# Sensor_Board_Schematic.net
KiCad netlist of a schematic drawn in Altium Designer
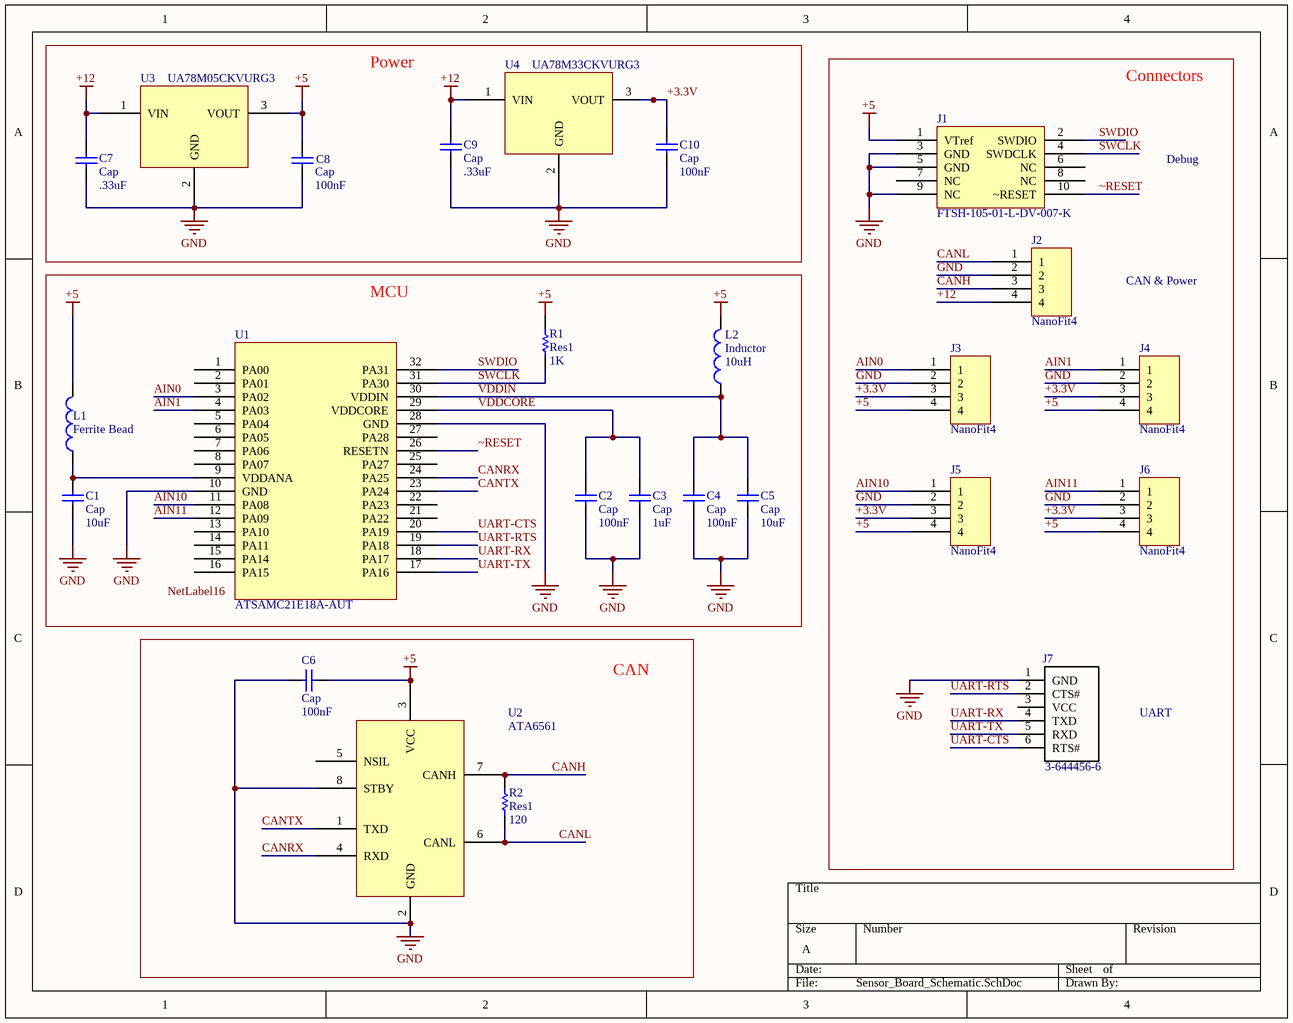
[diagram p0: Sensor_Board_Schematic.SchDoc]

(export (version "E")
  (design (tool "Eeschema 10.0.6"))
  (components
    (comp (ref "C1")
      (value "Cap")
      (footprint "Sensor_Board_Footprints:CAPC1608X08N")
      (description "Capacitor")
      (fields (field (name "ALTIUM_VALUE") "10uF") (field (name "PUBLISHER") "Altium Limited"))
      (libsource (lib "Miscellaneous Devices") (part "Cap"))
    )
    (comp (ref "C2")
      (value "Cap")
      (footprint "Sensor_Board_Footprints:CAPC1608X08N")
      (description "Capacitor")
      (fields (field (name "ALTIUM_VALUE") "100nF") (field (name "PUBLISHER") "Altium Limited"))
      (libsource (lib "Miscellaneous Devices") (part "Cap"))
    )
    (comp (ref "C3")
      (value "Cap")
      (footprint "Sensor_Board_Footprints:CAPC1608X08N")
      (description "Capacitor")
      (fields (field (name "ALTIUM_VALUE") "1uF") (field (name "PUBLISHER") "Altium Limited"))
      (libsource (lib "Miscellaneous Devices") (part "Cap"))
    )
    (comp (ref "C4")
      (value "Cap")
      (footprint "Sensor_Board_Footprints:CAPC1608X08N")
      (description "Capacitor")
      (fields (field (name "ALTIUM_VALUE") "100nF") (field (name "PUBLISHER") "Altium Limited"))
      (libsource (lib "Miscellaneous Devices") (part "Cap"))
    )
    (comp (ref "C5")
      (value "Cap")
      (footprint "Sensor_Board_Footprints:CAPC1608X08N")
      (description "Capacitor")
      (fields (field (name "ALTIUM_VALUE") "10uF") (field (name "PUBLISHER") "Altium Limited"))
      (libsource (lib "Miscellaneous Devices") (part "Cap"))
    )
    (comp (ref "C6")
      (value "Cap")
      (footprint "Sensor_Board_Footprints:CAPC1608X08N")
      (description "Capacitor")
      (fields (field (name "ALTIUM_VALUE") "100nF") (field (name "PUBLISHER") "Altium Limited"))
      (libsource (lib "Miscellaneous Devices") (part "Cap"))
    )
    (comp (ref "C7")
      (value "Cap")
      (footprint "Footprints:CAPC1608X08N")
      (description "Capacitor")
      (fields (field (name "ALTIUM_VALUE") ".33uF") (field (name "PUBLISHER") "Altium Limited"))
      (libsource (lib "Miscellaneous Devices") (part "Cap"))
    )
    (comp (ref "C8")
      (value "Cap")
      (footprint "Sensor_Board_Footprints:CAPC1608X08N")
      (description "Capacitor")
      (fields (field (name "ALTIUM_VALUE") "100nF") (field (name "PUBLISHER") "Altium Limited"))
      (libsource (lib "Miscellaneous Devices") (part "Cap"))
    )
    (comp (ref "C9")
      (value "Cap")
      (footprint "Footprints:CAPC1608X08N")
      (description "Capacitor")
      (fields (field (name "ALTIUM_VALUE") ".33uF") (field (name "PUBLISHER") "Altium Limited"))
      (libsource (lib "Miscellaneous Devices") (part "Cap"))
    )
    (comp (ref "C10")
      (value "Cap")
      (footprint "Footprints:CAPC1608X08N")
      (description "Capacitor")
      (fields (field (name "ALTIUM_VALUE") "100nF") (field (name "PUBLISHER") "Altium Limited"))
      (libsource (lib "Miscellaneous Devices") (part "Cap"))
    )
    (comp (ref "J1")
      (value "FTSH-105-01-L-DV-007-K")
      (footprint "Sensor_Board_Footprints:FTSH-105-01-L-DV-007-K")
      (libsource (lib "Parts2") (part "FTSH-105-01-L-DV-007-K"))
    )
    (comp (ref "J2")
      (value "NanoFit4")
      (footprint "Sensor_Board_Footprints:1053141304")
      (libsource (lib "Parts2") (part "NanoFit4"))
    )
    (comp (ref "J3")
      (value "NanoFit4")
      (footprint "Sensor_Board_Footprints:1053141304")
      (libsource (lib "Parts2") (part "NanoFit4"))
    )
    (comp (ref "J4")
      (value "NanoFit4")
      (footprint "Sensor_Board_Footprints:1053141304")
      (libsource (lib "Parts2") (part "NanoFit4"))
    )
    (comp (ref "J5")
      (value "NanoFit4")
      (footprint "Sensor_Board_Footprints:1053141304")
      (libsource (lib "Parts2") (part "NanoFit4"))
    )
    (comp (ref "J6")
      (value "NanoFit4")
      (footprint "Sensor_Board_Footprints:1053141304")
      (libsource (lib "Parts2") (part "NanoFit4"))
    )
    (comp (ref "J7")
      (value "3-644456-6")
      (footprint "*TE_3-644456-6")
      (libsource (lib "Sensor_Board_Schematics") (part "3-644456-6"))
    )
    (comp (ref "L1")
      (value "Ferrite Bead")
      (footprint "Sensor_Board_Footprints:INDC2012X11N")
      (description "Inductor")
      (fields (field (name "PUBLISHER") "Altium Limited"))
      (libsource (lib "Miscellaneous Devices") (part "Inductor"))
    )
    (comp (ref "L2")
      (value "Inductor")
      (footprint "Sensor_Board_Footprints:INDC2016X18N")
      (fields (field (name "ALTIUM_VALUE") "10uH") (field (name "PUBLISHER") "Altium Limited"))
      (libsource (lib "Miscellaneous Devices") (part "Inductor"))
    )
    (comp (ref "R1")
      (value "Res1")
      (footprint "Sensor_Board_Footprints:RESC1608X06N")
      (description "Resistor")
      (fields (field (name "ALTIUM_VALUE") "1K") (field (name "PUBLISHER") "Altium Limited"))
      (libsource (lib "Miscellaneous Devices") (part "Res1"))
    )
    (comp (ref "R2")
      (value "Res1")
      (footprint "Sensor_Board_Footprints:RESC1608X06N")
      (description "Resistor")
      (fields (field (name "ALTIUM_VALUE") "120") (field (name "PUBLISHER") "Altium Limited"))
      (libsource (lib "Miscellaneous Devices") (part "Res1"))
    )
    (comp (ref "U1")
      (value "ATSAMC21E18A-AUT")
      (footprint "Sensor_Board_Footprints:TQFP80P900X900X120-32N")
      (libsource (lib "Parts2") (part "ATSAMC21E18A-AUT"))
    )
    (comp (ref "U2")
      (value "ATA6561")
      (footprint "Sensor_Board_Footprints:SOIC127P600X175-8N")
      (libsource (lib "Parts2") (part "ATA6561"))
    )
    (comp (ref "U3")
      (value "UA78M05CKVURG3")
      (footprint "Sensor_Board_Footprints:DPAK229P991X252-3N")
      (libsource (lib "Parts2") (part "UA78M05CKVURG3"))
    )
    (comp (ref "U4")
      (value "UA78M33CKVURG3")
      (footprint "Sensor_Board_Footprints:DPAK229P991X252-3N")
      (libsource (lib "Parts2") (part "UA78M33CKVURG3"))
    )
  )
  (nets
    (net (code "1") (name "+5") (class "Default")
      (node (ref "C6") (pin "1") (pinfunction "1_1") (pintype "passive"))
      (node (ref "C8") (pin "1") (pinfunction "1_1") (pintype "passive"))
      (node (ref "J1") (pin "1") (pinfunction "VTref_1") (pintype "passive"))
      (node (ref "J3") (pin "4") (pinfunction "4_4") (pintype "passive"))
      (node (ref "J4") (pin "4") (pinfunction "4_4") (pintype "passive"))
      (node (ref "J5") (pin "4") (pinfunction "4_4") (pintype "passive"))
      (node (ref "J6") (pin "4") (pinfunction "4_4") (pintype "passive"))
      (node (ref "L1") (pin "2") (pinfunction "2_2") (pintype "passive"))
      (node (ref "L2") (pin "2") (pinfunction "2_2") (pintype "passive"))
      (node (ref "R1") (pin "2") (pinfunction "2_2") (pintype "passive"))
      (node (ref "U2") (pin "3") (pinfunction "VCC_3") (pintype "passive"))
      (node (ref "U3") (pin "3") (pinfunction "VOUT_3") (pintype "passive"))
    )
    (net (code "2") (name "+12") (class "Default")
      (node (ref "C7") (pin "1") (pinfunction "1_1") (pintype "passive"))
      (node (ref "C9") (pin "2") (pinfunction "2_2") (pintype "passive"))
      (node (ref "J2") (pin "4") (pinfunction "4_4") (pintype "passive"))
      (node (ref "U3") (pin "1") (pinfunction "VIN_1") (pintype "passive"))
      (node (ref "U4") (pin "1") (pinfunction "VIN_1") (pintype "passive"))
    )
    (net (code "3") (name "/+3.3V") (class "Default")
      (node (ref "C10") (pin "2") (pinfunction "2_2") (pintype "passive"))
      (node (ref "J3") (pin "3") (pinfunction "3_3") (pintype "passive"))
      (node (ref "J4") (pin "3") (pinfunction "3_3") (pintype "passive"))
      (node (ref "J5") (pin "3") (pinfunction "3_3") (pintype "passive"))
      (node (ref "J6") (pin "3") (pinfunction "3_3") (pintype "passive"))
      (node (ref "U4") (pin "3") (pinfunction "VOUT_3") (pintype "passive"))
    )
    (net (code "4") (name "/AIN0") (class "Default")
      (node (ref "J3") (pin "1") (pinfunction "1_1") (pintype "passive"))
      (node (ref "U1") (pin "3") (pinfunction "PA02_3") (pintype "passive"))
    )
    (net (code "5") (name "/AIN1") (class "Default")
      (node (ref "J4") (pin "1") (pinfunction "1_1") (pintype "passive"))
      (node (ref "U1") (pin "4") (pinfunction "PA03_4") (pintype "passive"))
    )
    (net (code "6") (name "/AIN10") (class "Default")
      (node (ref "J5") (pin "1") (pinfunction "1_1") (pintype "passive"))
      (node (ref "U1") (pin "11") (pinfunction "PA08_11") (pintype "passive"))
    )
    (net (code "7") (name "/AIN11") (class "Default")
      (node (ref "J6") (pin "1") (pinfunction "1_1") (pintype "passive"))
      (node (ref "U1") (pin "12") (pinfunction "PA09_12") (pintype "passive"))
    )
    (net (code "8") (name "/CANH") (class "Default")
      (node (ref "J2") (pin "3") (pinfunction "3_3") (pintype "passive"))
      (node (ref "R2") (pin "2") (pinfunction "2_2") (pintype "passive"))
      (node (ref "U2") (pin "7") (pinfunction "CANH_7") (pintype "passive"))
    )
    (net (code "9") (name "/CANL") (class "Default")
      (node (ref "J2") (pin "1") (pinfunction "1_1") (pintype "passive"))
      (node (ref "R2") (pin "1") (pinfunction "1_1") (pintype "passive"))
      (node (ref "U2") (pin "6") (pinfunction "CANL_6") (pintype "passive"))
    )
    (net (code "10") (name "/CANRX") (class "Default")
      (node (ref "U1") (pin "24") (pinfunction "PA25_24") (pintype "passive"))
      (node (ref "U2") (pin "4") (pinfunction "RXD_4") (pintype "passive"))
    )
    (net (code "11") (name "/CANTX") (class "Default")
      (node (ref "U1") (pin "23") (pinfunction "PA24_23") (pintype "passive"))
      (node (ref "U2") (pin "1") (pinfunction "TXD_1") (pintype "passive"))
    )
    (net (code "13") (name "/SWCLK") (class "Default")
      (node (ref "J1") (pin "4") (pinfunction "SWDCLK_4") (pintype "passive"))
      (node (ref "R1") (pin "1") (pinfunction "1_1") (pintype "passive"))
      (node (ref "U1") (pin "31") (pinfunction "PA30_31") (pintype "passive"))
    )
    (net (code "14") (name "/SWDIO") (class "Default")
      (node (ref "J1") (pin "2") (pinfunction "SWDIO_2") (pintype "passive"))
      (node (ref "U1") (pin "32") (pinfunction "PA31_32") (pintype "passive"))
    )
    (net (code "15") (name "/UART-CTS") (class "Default")
      (node (ref "J7") (pin "6") (pinfunction "RTS#_6") (pintype "passive"))
      (node (ref "U1") (pin "20") (pinfunction "PA19_20") (pintype "passive"))
    )
    (net (code "16") (name "/UART-RTS") (class "Default")
      (node (ref "J7") (pin "2") (pinfunction "CTS#_2") (pintype "passive"))
      (node (ref "U1") (pin "19") (pinfunction "PA18_19") (pintype "passive"))
    )
    (net (code "17") (name "/UART-RX") (class "Default")
      (node (ref "J7") (pin "4") (pinfunction "TXD_4") (pintype "passive"))
      (node (ref "U1") (pin "18") (pinfunction "PA17_18") (pintype "passive"))
    )
    (net (code "18") (name "/UART-TX") (class "Default")
      (node (ref "J7") (pin "5") (pinfunction "RXD_5") (pintype "passive"))
      (node (ref "U1") (pin "17") (pinfunction "PA16_17") (pintype "passive"))
    )
    (net (code "19") (name "/VDDCORE") (class "Default")
      (node (ref "C2") (pin "2") (pinfunction "2_2") (pintype "passive"))
      (node (ref "C3") (pin "2") (pinfunction "2_2") (pintype "passive"))
      (node (ref "U1") (pin "29") (pinfunction "VDDCORE_29") (pintype "passive"))
    )
    (net (code "20") (name "/VDDIN") (class "Default")
      (node (ref "C4") (pin "2") (pinfunction "2_2") (pintype "passive"))
      (node (ref "C5") (pin "2") (pinfunction "2_2") (pintype "passive"))
      (node (ref "L2") (pin "1") (pinfunction "1_1") (pintype "passive"))
      (node (ref "U1") (pin "30") (pinfunction "VDDIN_30") (pintype "passive"))
    )
    (net (code "21") (name "/~RESET") (class "Default")
      (node (ref "J1") (pin "10") (pinfunction "~RESET_10") (pintype "passive"))
      (node (ref "U1") (pin "26") (pinfunction "RESETN_26") (pintype "passive"))
    )
    (net (code "22") (name "GND") (class "Default")
      (node (ref "C1") (pin "1") (pinfunction "1_1") (pintype "passive"))
      (node (ref "C10") (pin "1") (pinfunction "1_1") (pintype "passive"))
      (node (ref "C2") (pin "1") (pinfunction "1_1") (pintype "passive"))
      (node (ref "C3") (pin "1") (pinfunction "1_1") (pintype "passive"))
      (node (ref "C4") (pin "1") (pinfunction "1_1") (pintype "passive"))
      (node (ref "C5") (pin "1") (pinfunction "1_1") (pintype "passive"))
      (node (ref "C6") (pin "2") (pinfunction "2_2") (pintype "passive"))
      (node (ref "C7") (pin "2") (pinfunction "2_2") (pintype "passive"))
      (node (ref "C8") (pin "2") (pinfunction "2_2") (pintype "passive"))
      (node (ref "C9") (pin "1") (pinfunction "1_1") (pintype "passive"))
      (node (ref "J1") (pin "3") (pinfunction "GND_3") (pintype "passive"))
      (node (ref "J1") (pin "5") (pinfunction "GND_5") (pintype "passive"))
      (node (ref "J1") (pin "9") (pinfunction "NC_9") (pintype "passive"))
      (node (ref "J2") (pin "2") (pinfunction "2_2") (pintype "passive"))
      (node (ref "J3") (pin "2") (pinfunction "2_2") (pintype "passive"))
      (node (ref "J4") (pin "2") (pinfunction "2_2") (pintype "passive"))
      (node (ref "J5") (pin "2") (pinfunction "2_2") (pintype "passive"))
      (node (ref "J6") (pin "2") (pinfunction "2_2") (pintype "passive"))
      (node (ref "J7") (pin "1") (pinfunction "GND_1") (pintype "passive"))
      (node (ref "U1") (pin "10") (pinfunction "GND_10") (pintype "passive"))
      (node (ref "U1") (pin "28") (pinfunction "GND_28") (pintype "passive"))
      (node (ref "U2") (pin "2") (pinfunction "GND_2") (pintype "passive"))
      (node (ref "U2") (pin "8") (pinfunction "STBY_8") (pintype "passive"))
      (node (ref "U3") (pin "2") (pinfunction "GND_2") (pintype "passive"))
      (node (ref "U4") (pin "2") (pinfunction "GND_2") (pintype "passive"))
    )
    (net (code "23") (name "Net-(U1-VDDANA)") (class "Default")
      (node (ref "C1") (pin "2") (pinfunction "2_2") (pintype "passive"))
      (node (ref "L1") (pin "1") (pinfunction "1_1") (pintype "passive"))
      (node (ref "U1") (pin "9") (pinfunction "VDDANA_9") (pintype "passive"))
    )
    (net (code "24") (name "unconnected-(J1-NC-Pad6)") (class "Default")
      (node (ref "J1") (pin "6") (pinfunction "NC_6") (pintype "passive"))
    )
    (net (code "25") (name "unconnected-(J1-NC-Pad7)") (class "Default")
      (node (ref "J1") (pin "7") (pinfunction "NC_7") (pintype "passive"))
    )
    (net (code "26") (name "unconnected-(J1-NC-Pad8)") (class "Default")
      (node (ref "J1") (pin "8") (pinfunction "NC_8") (pintype "passive"))
    )
    (net (code "27") (name "unconnected-(J7-VCC-Pad3)") (class "Default")
      (node (ref "J7") (pin "3") (pinfunction "VCC_3") (pintype "passive"))
    )
    (net (code "28") (name "unconnected-(U1-PA00-Pad1)") (class "Default")
      (node (ref "U1") (pin "1") (pinfunction "PA00_1") (pintype "passive"))
    )
    (net (code "29") (name "unconnected-(U1-PA01-Pad2)") (class "Default")
      (node (ref "U1") (pin "2") (pinfunction "PA01_2") (pintype "passive"))
    )
    (net (code "30") (name "unconnected-(U1-PA04-Pad5)") (class "Default")
      (node (ref "U1") (pin "5") (pinfunction "PA04_5") (pintype "passive"))
    )
    (net (code "31") (name "unconnected-(U1-PA05-Pad6)") (class "Default")
      (node (ref "U1") (pin "6") (pinfunction "PA05_6") (pintype "passive"))
    )
    (net (code "32") (name "unconnected-(U1-PA06-Pad7)") (class "Default")
      (node (ref "U1") (pin "7") (pinfunction "PA06_7") (pintype "passive"))
    )
    (net (code "33") (name "unconnected-(U1-PA07-Pad8)") (class "Default")
      (node (ref "U1") (pin "8") (pinfunction "PA07_8") (pintype "passive"))
    )
    (net (code "34") (name "unconnected-(U1-PA10-Pad13)") (class "Default")
      (node (ref "U1") (pin "13") (pinfunction "PA10_13") (pintype "passive"))
    )
    (net (code "35") (name "unconnected-(U1-PA11-Pad14)") (class "Default")
      (node (ref "U1") (pin "14") (pinfunction "PA11_14") (pintype "passive"))
    )
    (net (code "36") (name "unconnected-(U1-PA14-Pad15)") (class "Default")
      (node (ref "U1") (pin "15") (pinfunction "PA14_15") (pintype "passive"))
    )
    (net (code "37") (name "unconnected-(U1-PA15-Pad16)") (class "Default")
      (node (ref "U1") (pin "16") (pinfunction "PA15_16") (pintype "passive"))
    )
    (net (code "38") (name "unconnected-(U1-PA22-Pad21)") (class "Default")
      (node (ref "U1") (pin "21") (pinfunction "PA22_21") (pintype "passive"))
    )
    (net (code "39") (name "unconnected-(U1-PA23-Pad22)") (class "Default")
      (node (ref "U1") (pin "22") (pinfunction "PA23_22") (pintype "passive"))
    )
    (net (code "40") (name "unconnected-(U1-PA27-Pad25)") (class "Default")
      (node (ref "U1") (pin "25") (pinfunction "PA27_25") (pintype "passive"))
    )
    (net (code "41") (name "unconnected-(U1-PA28-Pad27)") (class "Default")
      (node (ref "U1") (pin "27") (pinfunction "PA28_27") (pintype "passive"))
    )
    (net (code "42") (name "unconnected-(U2-NSIL-Pad5)") (class "Default")
      (node (ref "U2") (pin "5") (pinfunction "NSIL_5") (pintype "passive"))
    )
  )
)
